# ushio_rp2040.net
KiCad netlist of a schematic drawn in Altium Designer
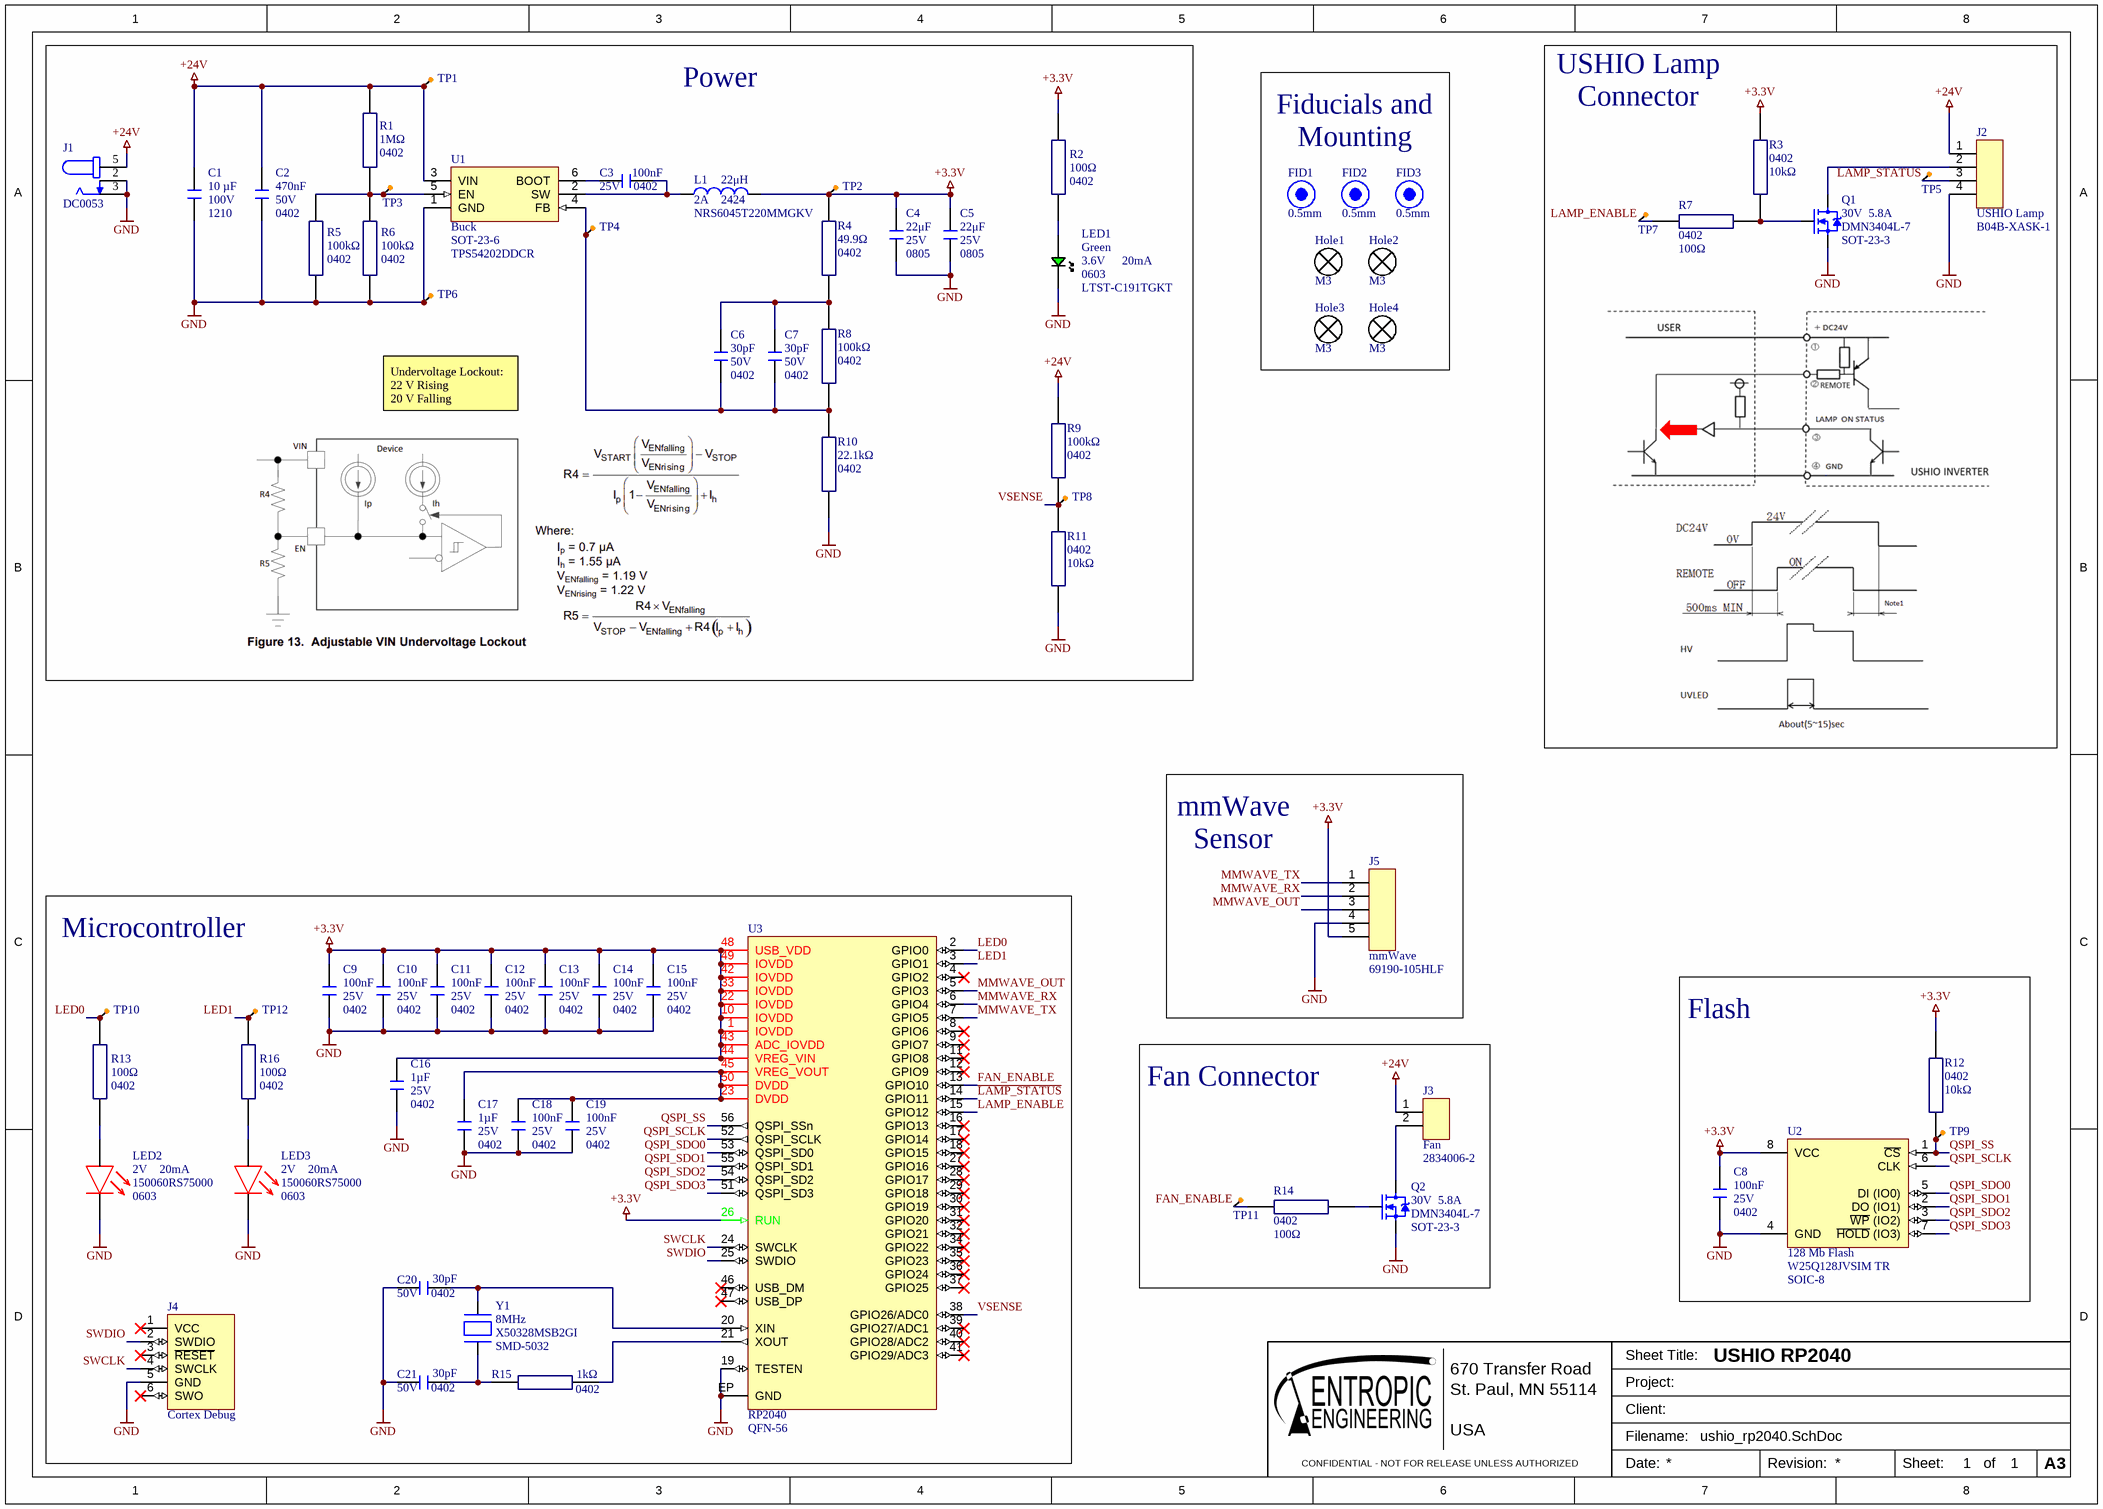
[diagram p0: ushio_rp2040.SchDoc]

(export (version "E")
  (design (tool "Eeschema 10.0.6"))
  (components
    (comp (ref "C1")
      (value "GRM32EC72A106KE05L")
      (footprint "1210_capacitor")
      (description "10 µF, 100 V, 1210 Ceramic capacitor")
      (fields
        (field (name "MANUFACTURER") "Murata")
        (field (name "TOLERANCE") "10%")
        (field (name "VOLTAGE RATING") "100V")
        (field (name "CASE/PACKAGE") "1210")
        (field (name "CAPACITANCE") "10 µF")
      )
      (libsource (lib "ushio_rp2040") (part "GRM32EC72A106KE05L"))
    )
    (comp (ref "C2")
      (value "GRM155R61H474KE11D")
      (footprint "0402_capacitor")
      (description "470 nF, 50 V, X5R, 0402 Chip capacitor")
      (fields
        (field (name "MANUFACTURER") "Murata")
        (field (name "TOLERANCE") "10%")
        (field (name "PACKAGE") "0402")
        (field (name "VOLTAGE RATING (DC)") "50V")
        (field (name "CAPACITANCE") "470nF")
      )
      (libsource (lib "ushio_rp2040") (part "GRM155R61H474KE11D"))
    )
    (comp (ref "C3")
      (value "GRM155R71E104KE14D")
      (footprint "0402_capacitor")
      (description "100 nF, 25 V, X7R, 0402 Chip capacitor")
      (fields
        (field (name "MANUFACTURER") "Murata")
        (field (name "TOLERANCE") "10%")
        (field (name "CASE CODE (IMPERIAL)") "0402")
        (field (name "VOLTAGE") "25V")
        (field (name "CAPACITANCE") "100nF")
      )
      (libsource (lib "ushio_rp2040") (part "GRM155R71E104KE14D"))
    )
    (comp (ref "C4")
      (value "22μF")
      (footprint "0805_capacitor")
      (description "22 μF, 25 V, X5R, 0805 Chip capacitor")
      (fields
        (field (name "MANUFACTURER") "Murata")
        (field (name "MANUFACTURER PART NUMBER") "GRT21BR61E226ME13L")
        (field (name "RATED DC VOLTAGE (URDC)") "25V")
        (field (name "CASE/PACKAGE") "0805")
      )
      (libsource (lib "lamp_controller") (part "GRT21BR61E226ME13L"))
    )
    (comp (ref "C5")
      (value "22μF")
      (footprint "0805_capacitor")
      (description "22 μF, 25 V, X5R, 0805 Chip capacitor")
      (fields
        (field (name "MANUFACTURER") "Murata")
        (field (name "MANUFACTURER PART NUMBER") "GRT21BR61E226ME13L")
        (field (name "RATED DC VOLTAGE (URDC)") "25V")
        (field (name "CASE/PACKAGE") "0805")
      )
      (libsource (lib "lamp_controller") (part "GRT21BR61E226ME13L"))
    )
    (comp (ref "C6")
      (value "30pF")
      (footprint "0402_capacitor")
      (description "30 pF, 50 V, C0G, 0402 Chip capacitor")
      (fields
        (field (name "MANUFACTURER") "Murata")
        (field (name "MANUFACTURER PART NUMBER") "GCM1555C1H300FA16D")
        (field (name "RATED DC VOLTAGE (URDC)") "50V")
        (field (name "CASE/PACKAGE") "0402")
      )
      (libsource (lib "ushio_rp2040") (part "GCM1555C1H300FA16D"))
    )
    (comp (ref "C7")
      (value "30pF")
      (footprint "0402_capacitor")
      (description "30 pF, 50 V, C0G, 0402 Chip capacitor")
      (fields
        (field (name "MANUFACTURER") "Murata")
        (field (name "MANUFACTURER PART NUMBER") "GCM1555C1H300FA16D")
        (field (name "RATED DC VOLTAGE (URDC)") "50V")
        (field (name "CASE/PACKAGE") "0402")
      )
      (libsource (lib "ushio_rp2040") (part "GCM1555C1H300FA16D"))
    )
    (comp (ref "C8")
      (value "GRM155R71E104KE14D")
      (footprint "0402_capacitor")
      (description "100 nF, 25 V, X7R, 0402 Chip capacitor")
      (fields
        (field (name "MANUFACTURER") "Murata")
        (field (name "TOLERANCE") "10%")
        (field (name "CASE CODE (IMPERIAL)") "0402")
        (field (name "VOLTAGE") "25V")
        (field (name "CAPACITANCE") "100nF")
      )
      (libsource (lib "ushio_rp2040") (part "GRM155R71E104KE14D"))
    )
    (comp (ref "C9")
      (value "GRM155R71E104KE14D")
      (footprint "0402_capacitor")
      (description "100 nF, 25 V, X7R, 0402 Chip capacitor")
      (fields
        (field (name "MANUFACTURER") "Murata")
        (field (name "TOLERANCE") "10%")
        (field (name "CASE CODE (IMPERIAL)") "0402")
        (field (name "VOLTAGE") "25V")
        (field (name "CAPACITANCE") "100nF")
      )
      (libsource (lib "ushio_rp2040") (part "GRM155R71E104KE14D"))
    )
    (comp (ref "C10")
      (value "GRM155R71E104KE14D")
      (footprint "0402_capacitor")
      (description "100 nF, 25 V, X7R, 0402 Chip capacitor")
      (fields
        (field (name "MANUFACTURER") "Murata")
        (field (name "TOLERANCE") "10%")
        (field (name "CASE CODE (IMPERIAL)") "0402")
        (field (name "VOLTAGE") "25V")
        (field (name "CAPACITANCE") "100nF")
      )
      (libsource (lib "ushio_rp2040") (part "GRM155R71E104KE14D"))
    )
    (comp (ref "C11")
      (value "GRM155R71E104KE14D")
      (footprint "0402_capacitor")
      (description "100 nF, 25 V, X7R, 0402 Chip capacitor")
      (fields
        (field (name "MANUFACTURER") "Murata")
        (field (name "TOLERANCE") "10%")
        (field (name "CASE CODE (IMPERIAL)") "0402")
        (field (name "VOLTAGE") "25V")
        (field (name "CAPACITANCE") "100nF")
      )
      (libsource (lib "ushio_rp2040") (part "GRM155R71E104KE14D"))
    )
    (comp (ref "C12")
      (value "GRM155R71E104KE14D")
      (footprint "0402_capacitor")
      (description "100 nF, 25 V, X7R, 0402 Chip capacitor")
      (fields
        (field (name "MANUFACTURER") "Murata")
        (field (name "TOLERANCE") "10%")
        (field (name "CASE CODE (IMPERIAL)") "0402")
        (field (name "VOLTAGE") "25V")
        (field (name "CAPACITANCE") "100nF")
      )
      (libsource (lib "ushio_rp2040") (part "GRM155R71E104KE14D"))
    )
    (comp (ref "C13")
      (value "GRM155R71E104KE14D")
      (footprint "0402_capacitor")
      (description "100 nF, 25 V, X7R, 0402 Chip capacitor")
      (fields
        (field (name "MANUFACTURER") "Murata")
        (field (name "TOLERANCE") "10%")
        (field (name "CASE CODE (IMPERIAL)") "0402")
        (field (name "VOLTAGE") "25V")
        (field (name "CAPACITANCE") "100nF")
      )
      (libsource (lib "ushio_rp2040") (part "GRM155R71E104KE14D"))
    )
    (comp (ref "C14")
      (value "GRM155R71E104KE14D")
      (footprint "0402_capacitor")
      (description "100 nF, 25 V, X7R, 0402 Chip capacitor")
      (fields
        (field (name "MANUFACTURER") "Murata")
        (field (name "TOLERANCE") "10%")
        (field (name "CASE CODE (IMPERIAL)") "0402")
        (field (name "VOLTAGE") "25V")
        (field (name "CAPACITANCE") "100nF")
      )
      (libsource (lib "ushio_rp2040") (part "GRM155R71E104KE14D"))
    )
    (comp (ref "C15")
      (value "GRM155R71E104KE14D")
      (footprint "0402_capacitor")
      (description "100 nF, 25 V, X7R, 0402 Chip capacitor")
      (fields
        (field (name "MANUFACTURER") "Murata")
        (field (name "TOLERANCE") "10%")
        (field (name "CASE CODE (IMPERIAL)") "0402")
        (field (name "VOLTAGE") "25V")
        (field (name "CAPACITANCE") "100nF")
      )
      (libsource (lib "ushio_rp2040") (part "GRM155R71E104KE14D"))
    )
    (comp (ref "C16")
      (value "GRM155R61E105KA12D")
      (footprint "0402_capacitor")
      (description "1 µF, 25 V, X5R, 0402 Chip capacitor")
      (fields
        (field (name "MANUFACTURER") "Murata")
        (field (name "HOUSE_PART_NUMBER") "C-1uF-0402-002")
        (field (name "SIZE CODE") "0402")
        (field (name "CAPACITANCE") "1µF")
        (field (name "VOLTAGE") "25V")
      )
      (libsource (lib "ushio_rp2040") (part "GRM155R61E105KA12D"))
    )
    (comp (ref "C17")
      (value "GRM155R61E105KA12D")
      (footprint "0402_capacitor")
      (description "1 µF, 25 V, X5R, 0402 Chip capacitor")
      (fields
        (field (name "MANUFACTURER") "Murata")
        (field (name "HOUSE_PART_NUMBER") "C-1uF-0402-002")
        (field (name "SIZE CODE") "0402")
        (field (name "CAPACITANCE") "1µF")
        (field (name "VOLTAGE") "25V")
      )
      (libsource (lib "ushio_rp2040") (part "GRM155R61E105KA12D"))
    )
    (comp (ref "C18")
      (value "GRM155R71E104KE14D")
      (footprint "0402_capacitor")
      (description "100 nF, 25 V, X7R, 0402 Chip capacitor")
      (fields
        (field (name "MANUFACTURER") "Murata")
        (field (name "TOLERANCE") "10%")
        (field (name "CASE CODE (IMPERIAL)") "0402")
        (field (name "VOLTAGE") "25V")
        (field (name "CAPACITANCE") "100nF")
      )
      (libsource (lib "ushio_rp2040") (part "GRM155R71E104KE14D"))
    )
    (comp (ref "C19")
      (value "GRM155R71E104KE14D")
      (footprint "0402_capacitor")
      (description "100 nF, 25 V, X7R, 0402 Chip capacitor")
      (fields
        (field (name "MANUFACTURER") "Murata")
        (field (name "TOLERANCE") "10%")
        (field (name "CASE CODE (IMPERIAL)") "0402")
        (field (name "VOLTAGE") "25V")
        (field (name "CAPACITANCE") "100nF")
      )
      (libsource (lib "ushio_rp2040") (part "GRM155R71E104KE14D"))
    )
    (comp (ref "C20")
      (value "30pF")
      (footprint "0402_capacitor")
      (description "30 pF, 50 V, C0G, 0402 Chip capacitor")
      (fields
        (field (name "MANUFACTURER") "Murata")
        (field (name "MANUFACTURER PART NUMBER") "GCM1555C1H300FA16D")
        (field (name "RATED DC VOLTAGE (URDC)") "50V")
        (field (name "CASE/PACKAGE") "0402")
      )
      (libsource (lib "ushio_rp2040") (part "GCM1555C1H300FA16D"))
    )
    (comp (ref "C21")
      (value "30pF")
      (footprint "0402_capacitor")
      (description "30 pF, 50 V, C0G, 0402 Chip capacitor")
      (fields
        (field (name "MANUFACTURER") "Murata")
        (field (name "MANUFACTURER PART NUMBER") "GCM1555C1H300FA16D")
        (field (name "RATED DC VOLTAGE (URDC)") "50V")
        (field (name "CASE/PACKAGE") "0402")
      )
      (libsource (lib "ushio_rp2040") (part "GCM1555C1H300FA16D"))
    )
    (comp (ref "FID1")
      (value "FID?")
      (footprint "fiducial-0.5")
      (description "0.5mm round fiducial")
      (fields (field (name "PACKAGE") "0.5mm"))
      (libsource (lib "ushio_rp2040") (part "fiducial-0.5"))
    )
    (comp (ref "FID2")
      (value "FID?")
      (footprint "fiducial-0.5")
      (description "0.5mm round fiducial")
      (fields (field (name "PACKAGE") "0.5mm"))
      (libsource (lib "ushio_rp2040") (part "fiducial-0.5"))
    )
    (comp (ref "FID3")
      (value "FID?")
      (footprint "fiducial-0.5")
      (description "0.5mm round fiducial")
      (fields (field (name "PACKAGE") "0.5mm"))
      (libsource (lib "ushio_rp2040") (part "fiducial-0.5"))
    )
    (comp (ref "Hole1")
      (value "M3")
      (footprint "m3_hole_no_pad")
      (description "M3 clearance hole")
      (libsource (lib "ushio_rp2040") (part "m3_hole_no_pad"))
    )
    (comp (ref "Hole2")
      (value "M3")
      (footprint "m3_hole_no_pad")
      (description "M3 clearance hole")
      (libsource (lib "ushio_rp2040") (part "m3_hole_no_pad"))
    )
    (comp (ref "Hole3")
      (value "M3")
      (footprint "m3_hole_no_pad")
      (description "M3 clearance hole")
      (libsource (lib "ushio_rp2040") (part "m3_hole_no_pad"))
    )
    (comp (ref "Hole4")
      (value "M3")
      (footprint "m3_hole_no_pad")
      (description "M3 clearance hole")
      (libsource (lib "ushio_rp2040") (part "m3_hole_no_pad"))
    )
    (comp (ref "J1")
      (value "DC0053")
      (footprint "DC0053")
      (description "5.5 mm x 2 mm Barrel jack")
      (fields (field (name "MANUFACTURER") "SHOU HAN") (field (name "MANUFACTURER PART NUMBER") "DC0053"))
      (libsource (lib "ushio_rp2040") (part "DC0053"))
    )
    (comp (ref "J2")
      (value "USHIO Lamp")
      (footprint "B04B-XASK-1")
      (description "4-pin JST XA header, 2.5mm pitch, through-hole")
      (fields (field (name "MANUFACTURER") "JST") (field (name "MANUFACTURER PART NUMBER") "B04B-XASK-1"))
      (libsource (lib "ushio_rp2040") (part "B04B-XASK-1"))
    )
    (comp (ref "J3")
      (value "Fan")
      (footprint "2834006-2")
      (description "2-Pin Barrier Strip Terminal Block")
      (fields
        (field (name "MANUFACTURER") "TE Connectivity")
        (field (name "MANUFACTURER PART NUMBER") "2834006-2")
      )
      (libsource (lib "ushio_rp2040") (part "2834006-2"))
    )
    (comp (ref "J4")
      (value "Cortex Debug")
      (footprint "debug_header")
      (description "Tag-connect 6-pin pogo header")
      (libsource (lib "ushio_rp2040") (part "debug_header"))
    )
    (comp (ref "J5")
      (value "mmWave")
      (footprint "69190-105HLF")
      (description "5-pin 0.1\" unshrouded header pins")
      (fields
        (field (name "MANUFACTURER") "Amphenol ICC / FCI")
        (field (name "MANUFACTURER PART NUMBER") "69190-105HLF")
      )
      (libsource (lib "ushio_rp2040") (part "69190-105HLF"))
    )
    (comp (ref "L1")
      (value "NRS6045T220MMGKV")
      (footprint "2424_inductor")
      (description "22 μH, 2 A, 20%, 2424 Inductor")
      (fields
        (field (name "MANUFACTURER") "Taiyo Yuden")
        (field (name "TOLERANCE") "20%")
        (field (name "MANUFACTURER PART NUMBER") "NRS6045T220MMGKV")
        (field (name "CASE/SIZE CODE") "2424")
        (field (name "MAX CURRENT RATING") "2A")
        (field (name "INDUCTANCE-NOM (L)") "22μH")
      )
      (libsource (lib "lamp_controller") (part "NRS6045T220MMGKV"))
    )
    (comp (ref "LED1")
      (value "LTST-C191TGKT")
      (footprint "0603_diode")
      (description "Green LED, 0603")
      (fields
        (field (name "MANUFACTURER") "Vishay Lite-On")
        (field (name "FORWARD CURRENT-MAX") "20mA")
        (field (name "FORWARD VOLTAGE-MAX") "3.6V")
        (field (name "COLOR") "Green")
        (field (name "PACKAGE") "0603")
        (field (name "MANUFACTURER PART NUMBER") "LTST-C191TGKT")
      )
      (libsource (lib "lamp_control") (part "LTST-C191TGKT"))
    )
    (comp (ref "LED2")
      (value "150060RS75000")
      (footprint "0603_diode")
      (description "Red 0603 LED")
      (fields
        (field (name "MANUFACTURER") "Wurth Electronics")
        (field (name "HOUSE_PART_NUMBER") "LED-red-0603-002")
        (field (name "FORWARD CURRENT") "20mA")
        (field (name "FORWARD VOLTAGE") "2V")
        (field (name "PACKAGE") "0603")
        (field (name "MANUFACTURER PART NUMBER") "150060RS75000")
      )
      (libsource (lib "advanced_wireless_6950_dock") (part "150060RS75000"))
    )
    (comp (ref "LED3")
      (value "150060RS75000")
      (footprint "0603_diode")
      (description "Red 0603 LED")
      (fields
        (field (name "MANUFACTURER") "Wurth Electronics")
        (field (name "HOUSE_PART_NUMBER") "LED-red-0603-002")
        (field (name "FORWARD CURRENT") "20mA")
        (field (name "FORWARD VOLTAGE") "2V")
        (field (name "PACKAGE") "0603")
        (field (name "MANUFACTURER PART NUMBER") "150060RS75000")
      )
      (libsource (lib "advanced_wireless_6950_dock") (part "150060RS75000"))
    )
    (comp (ref "Q1")
      (value "DMN3404L-7")
      (footprint "SOT-23-3")
      (description "N-FET, 30 V, 5.8 A, SOT-23-3")
      (fields
        (field (name "MANUFACTURER") "Diodes")
        (field (name "PACKAGE") "SOT-23-3")
        (field (name "DS BREAKDOWN VOLTAGE-MIN") "30V")
        (field (name "DRAIN CURRENT-MAX (ID)") "5.8A")
        (field (name "MANUFACTURER PART NUMBER") "DMN3404L-7")
      )
      (libsource (lib "ushio_rp2040") (part "DMN3404L-7"))
    )
    (comp (ref "Q2")
      (value "DMN3404L-7")
      (footprint "SOT-23-3")
      (description "N-FET, 30 V, 5.8 A, SOT-23-3")
      (fields
        (field (name "MANUFACTURER") "Diodes")
        (field (name "PACKAGE") "SOT-23-3")
        (field (name "DS BREAKDOWN VOLTAGE-MIN") "30V")
        (field (name "DRAIN CURRENT-MAX (ID)") "5.8A")
        (field (name "MANUFACTURER PART NUMBER") "DMN3404L-7")
      )
      (libsource (lib "ushio_rp2040") (part "DMN3404L-7"))
    )
    (comp (ref "R1")
      (value "RC0402FR-071ML")
      (footprint "0402_resistor")
      (description "1 MΩ, 1%, 0402 Resistor")
      (fields
        (field (name "MANUFACTURER") "Yageo")
        (field (name "TOLERANCE") "1%")
        (field (name "SIZE CODE") "0402")
        (field (name "RESISTANCE") "1MΩ")
      )
      (libsource (lib "ushio_rp2040") (part "RC0402FR-071ML"))
    )
    (comp (ref "R2")
      (value "RMCF0402FT100R")
      (footprint "0402_resistor")
      (description "100 Ω, 0402 Chip resistor")
      (fields
        (field (name "MANUFACTURER") "Stackpole Electronics")
        (field (name "TOLERANCE") "1%")
        (field (name "CASE CODE (IMPERIAL)") "0402")
        (field (name "RESISTANCE") "100Ω")
      )
      (libsource (lib "ushio_rp2040") (part "RMCF0402FT100R"))
    )
    (comp (ref "R3")
      (value "RMCF0402FT10K0")
      (footprint "0402_resistor")
      (description "10 kΩ, 0402 Chip resistor")
      (fields
        (field (name "MANUFACTURER") "Stackpole Electronics")
        (field (name "TOLERANCE") "1%")
        (field (name "CASE CODE (IMPERIAL)") "0402")
        (field (name "RESISTANCE") "10kΩ")
      )
      (libsource (lib "ushio_rp2040") (part "RMCF0402FT10K0"))
    )
    (comp (ref "R4")
      (value "RMCF0402FT49R9")
      (footprint "0402_resistor")
      (description "49.9 Ω, 0402 Chip resistor")
      (fields
        (field (name "MANUFACTURER") "Stackpole Electronics")
        (field (name "TOLERANCE") "1%")
        (field (name "RESISTANCE") "49.9Ω")
        (field (name "CASE CODE (IMPERIAL)") "0402")
      )
      (libsource (lib "ushio_rp2040") (part "RMCF0402FT49R9"))
    )
    (comp (ref "R5")
      (value "100kΩ")
      (footprint "0402_resistor")
      (description "100 kΩ, 0402 Chip resistor")
      (fields
        (field (name "MANUFACTURER") "Stackpole Electronics")
        (field (name "MANUFACTURER PART NUMBER") "RMCF0402FT100K")
        (field (name "CASE/PACKAGE") "0402")
      )
      (libsource (lib "lamp_controller") (part "RMCF0402FT100K"))
    )
    (comp (ref "R6")
      (value "100kΩ")
      (footprint "0402_resistor")
      (description "100 kΩ, 0402 Chip resistor")
      (fields
        (field (name "MANUFACTURER") "Stackpole Electronics")
        (field (name "MANUFACTURER PART NUMBER") "RMCF0402FT100K")
        (field (name "CASE/PACKAGE") "0402")
      )
      (libsource (lib "lamp_controller") (part "RMCF0402FT100K"))
    )
    (comp (ref "R7")
      (value "RMCF0402FT100R")
      (footprint "0402_resistor")
      (description "100 Ω, 0402 Chip resistor")
      (fields
        (field (name "MANUFACTURER") "Stackpole Electronics")
        (field (name "TOLERANCE") "1%")
        (field (name "CASE CODE (IMPERIAL)") "0402")
        (field (name "RESISTANCE") "100Ω")
      )
      (libsource (lib "ushio_rp2040") (part "RMCF0402FT100R"))
    )
    (comp (ref "R8")
      (value "100kΩ")
      (footprint "0402_resistor")
      (description "100 kΩ, 0402 Chip resistor")
      (fields
        (field (name "MANUFACTURER") "Stackpole Electronics")
        (field (name "MANUFACTURER PART NUMBER") "RMCF0402FT100K")
        (field (name "CASE/PACKAGE") "0402")
      )
      (libsource (lib "lamp_controller") (part "RMCF0402FT100K"))
    )
    (comp (ref "R9")
      (value "100kΩ")
      (footprint "0402_resistor")
      (description "100 kΩ, 0402 Chip resistor")
      (fields
        (field (name "MANUFACTURER") "Stackpole Electronics")
        (field (name "MANUFACTURER PART NUMBER") "RMCF0402FT100K")
        (field (name "CASE/PACKAGE") "0402")
      )
      (libsource (lib "lamp_controller") (part "RMCF0402FT100K"))
    )
    (comp (ref "R10")
      (value "22.1kΩ")
      (footprint "0402_resistor")
      (description "22.1 kΩ, 1%, 0402 Chip resistor")
      (fields
        (field (name "MANUFACTURER") "Stackpole Electronics")
        (field (name "MANUFACTURER PART NUMBER") "RMCF0402FT22K1")
        (field (name "CASE/PACKAGE") "0402")
      )
      (libsource (lib "lamp_controller") (part "RMCF0402FT22K1"))
    )
    (comp (ref "R11")
      (value "RMCF0402FT10K0")
      (footprint "0402_resistor")
      (description "10 kΩ, 0402 Chip resistor")
      (fields
        (field (name "MANUFACTURER") "Stackpole Electronics")
        (field (name "TOLERANCE") "1%")
        (field (name "CASE CODE (IMPERIAL)") "0402")
        (field (name "RESISTANCE") "10kΩ")
      )
      (libsource (lib "ushio_rp2040") (part "RMCF0402FT10K0"))
    )
    (comp (ref "R12")
      (value "RMCF0402FT10K0")
      (footprint "0402_resistor")
      (description "10 kΩ, 0402 Chip resistor")
      (fields
        (field (name "MANUFACTURER") "Stackpole Electronics")
        (field (name "TOLERANCE") "1%")
        (field (name "CASE CODE (IMPERIAL)") "0402")
        (field (name "RESISTANCE") "10kΩ")
      )
      (libsource (lib "ushio_rp2040") (part "RMCF0402FT10K0"))
    )
    (comp (ref "R13")
      (value "RMCF0402FT100R")
      (footprint "0402_resistor")
      (description "100 Ω, 0402 Chip resistor")
      (fields
        (field (name "MANUFACTURER") "Stackpole Electronics")
        (field (name "TOLERANCE") "1%")
        (field (name "CASE CODE (IMPERIAL)") "0402")
        (field (name "RESISTANCE") "100Ω")
      )
      (libsource (lib "ushio_rp2040") (part "RMCF0402FT100R"))
    )
    (comp (ref "R14")
      (value "RMCF0402FT100R")
      (footprint "0402_resistor")
      (description "100 Ω, 0402 Chip resistor")
      (fields
        (field (name "MANUFACTURER") "Stackpole Electronics")
        (field (name "TOLERANCE") "1%")
        (field (name "CASE CODE (IMPERIAL)") "0402")
        (field (name "RESISTANCE") "100Ω")
      )
      (libsource (lib "ushio_rp2040") (part "RMCF0402FT100R"))
    )
    (comp (ref "R15")
      (value "CR0402-FX-1001GLF")
      (footprint "0402_resistor")
      (description "1 kΩ, 0402 Chip resistor")
      (fields
        (field (name "MANUFACTURER") "Bourns")
        (field (name "TOLERANCE") "1%")
        (field (name "SIZE CODE") "0402")
        (field (name "RESISTANCE") "1kΩ")
      )
      (libsource (lib "ushio_rp2040") (part "CR0402-FX-1001GLF"))
    )
    (comp (ref "R16")
      (value "RMCF0402FT100R")
      (footprint "0402_resistor")
      (description "100 Ω, 0402 Chip resistor")
      (fields
        (field (name "MANUFACTURER") "Stackpole Electronics")
        (field (name "TOLERANCE") "1%")
        (field (name "CASE CODE (IMPERIAL)") "0402")
        (field (name "RESISTANCE") "100Ω")
      )
      (libsource (lib "ushio_rp2040") (part "RMCF0402FT100R"))
    )
    (comp (ref "TP1")
      (value "test_point-1")
      (footprint "test_point-1")
      (description "Test point")
      (libsource (lib "ushio_rp2040") (part "test_point-1"))
    )
    (comp (ref "TP2")
      (value "test_point-1")
      (footprint "test_point-1")
      (description "Test point")
      (libsource (lib "ushio_rp2040") (part "test_point-1"))
    )
    (comp (ref "TP3")
      (value "test_point-1")
      (footprint "test_point-1")
      (description "Test point")
      (libsource (lib "ushio_rp2040") (part "test_point-1"))
    )
    (comp (ref "TP4")
      (value "test_point-1")
      (footprint "test_point-1")
      (description "Test point")
      (libsource (lib "ushio_rp2040") (part "test_point-1"))
    )
    (comp (ref "TP5")
      (value "test_point-1")
      (footprint "test_point-1")
      (description "Test point")
      (libsource (lib "ushio_rp2040") (part "test_point-1"))
    )
    (comp (ref "TP6")
      (value "test_point-1")
      (footprint "test_point-1")
      (description "Test point")
      (libsource (lib "ushio_rp2040") (part "test_point-1"))
    )
    (comp (ref "TP7")
      (value "test_point-1")
      (footprint "test_point-1")
      (description "Test point")
      (libsource (lib "ushio_rp2040") (part "test_point-1"))
    )
    (comp (ref "TP8")
      (value "test_point-1")
      (footprint "test_point-1")
      (description "Test point")
      (libsource (lib "ushio_rp2040") (part "test_point-1"))
    )
    (comp (ref "TP9")
      (value "test_point-1")
      (footprint "test_point-1")
      (description "Test point")
      (libsource (lib "ushio_rp2040") (part "test_point-1"))
    )
    (comp (ref "TP10")
      (value "test_point-1")
      (footprint "test_point-1")
      (description "Test point")
      (libsource (lib "ushio_rp2040") (part "test_point-1"))
    )
    (comp (ref "TP11")
      (value "test_point-1")
      (footprint "test_point-1")
      (description "Test point")
      (libsource (lib "ushio_rp2040") (part "test_point-1"))
    )
    (comp (ref "TP12")
      (value "test_point-1")
      (footprint "test_point-1")
      (description "Test point")
      (libsource (lib "ushio_rp2040") (part "test_point-1"))
    )
    (comp (ref "U1")
      (value "Buck")
      (footprint "SOT-23-6")
      (description "Switching Regulator, Current-mode, 2A, 500kHz Switching Freq-Max, PDSO6")
      (fields
        (field (name "MANUFACTURER") "Texas Instruments")
        (field (name "CASE/PACKAGE") "SOT-23-6")
        (field (name "MANUFACTURER PART NUMBER") "TPS54202DDCR")
      )
      (libsource (lib "ushio_rp2040") (part "TPS54202DDCR"))
    )
    (comp (ref "U2")
      (value "128 Mb Flash")
      (footprint "SOIC-8_wide")
      (description "128Mb SPI flash memory")
      (fields
        (field (name "MANUFACTURER") "Winbond")
        (field (name "HOUSE_PART_NUMBER") "W25Q128JVSIM")
        (field (name "MANUFACTURER PART NUMBER") "W25Q128JVSIM TR")
        (field (name "CASE/PACKAGE") "SOIC-8")
      )
      (libsource (lib "ushio_rp2040") (part "W25Q128JVSIM TR"))
    )
    (comp (ref "U3")
      (value "RP2040")
      (footprint "QFN-56")
      (description "Raspberry Pi microcontroller, QFN-56")
      (fields
        (field (name "MANUFACTURER") "Raspberry Pi")
        (field (name "MANUFACTURER PART NUMBER") "RP2040")
        (field (name "PACKAGE") "QFN-56")
      )
      (libsource (lib "ushio_rp2040") (part "RP2040"))
    )
    (comp (ref "Y1")
      (value "X50328MSB2GI")
      (footprint "SMD-5032")
      (description "8 MHz crystal, 20 pF, ±50ppm, SMD-5032")
      (fields
        (field (name "MANUFACTURER") "YXC")
        (field (name "FREQUENCY") "8MHz")
        (field (name "PACKAGE") "SMD-5032")
        (field (name "MANUFACTURER PART NUMBER") "X50328MSB2GI")
      )
      (libsource (lib "ushio_rp2040") (part "X50328MSB2GI"))
    )
  )
  (nets
    (net (code "1") (name "+3.3V") (class "Default")
      (node (ref "C10") (pin "2") (pinfunction "2_2") (pintype "passive"))
      (node (ref "C11") (pin "2") (pinfunction "2_2") (pintype "passive"))
      (node (ref "C12") (pin "2") (pinfunction "2_2") (pintype "passive"))
      (node (ref "C13") (pin "2") (pinfunction "2_2") (pintype "passive"))
      (node (ref "C14") (pin "2") (pinfunction "2_2") (pintype "passive"))
      (node (ref "C15") (pin "2") (pinfunction "2_2") (pintype "passive"))
      (node (ref "C16") (pin "2") (pinfunction "2_2") (pintype "passive"))
      (node (ref "C4") (pin "2") (pinfunction "2_2") (pintype "passive"))
      (node (ref "C5") (pin "2") (pinfunction "2_2") (pintype "passive"))
      (node (ref "C8") (pin "2") (pinfunction "2_2") (pintype "passive"))
      (node (ref "C9") (pin "2") (pinfunction "2_2") (pintype "passive"))
      (node (ref "J5") (pin "5") (pintype "passive"))
      (node (ref "L1") (pin "2") (pinfunction "2_2") (pintype "passive"))
      (node (ref "R12") (pin "2") (pinfunction "2_2") (pintype "passive"))
      (node (ref "R2") (pin "2") (pinfunction "2_2") (pintype "passive"))
      (node (ref "R3") (pin "1") (pinfunction "1_1") (pintype "passive"))
      (node (ref "R4") (pin "2") (pinfunction "2_2") (pintype "passive"))
      (node (ref "TP2") (pin "1") (pinfunction "1_1") (pintype "passive"))
      (node (ref "U2") (pin "8") (pinfunction "VCC_8") (pintype "power_in"))
      (node (ref "U3") (pin "1") (pinfunction "IOVDD_1") (pintype "power_in"))
      (node (ref "U3") (pin "10") (pinfunction "IOVDD_10") (pintype "power_in"))
      (node (ref "U3") (pin "22") (pinfunction "IOVDD_22") (pintype "power_in"))
      (node (ref "U3") (pin "26") (pinfunction "RUN_26") (pintype "input"))
      (node (ref "U3") (pin "33") (pinfunction "IOVDD_33") (pintype "power_in"))
      (node (ref "U3") (pin "42") (pinfunction "IOVDD_42") (pintype "power_in"))
      (node (ref "U3") (pin "43") (pinfunction "ADC_IOVDD_43") (pintype "power_in"))
      (node (ref "U3") (pin "44") (pinfunction "VREG_VIN_44") (pintype "power_in"))
      (node (ref "U3") (pin "48") (pinfunction "USB_VDD_48") (pintype "power_in"))
      (node (ref "U3") (pin "49") (pinfunction "IOVDD_49") (pintype "power_in"))
    )
    (net (code "2") (name "+24V") (class "Default")
      (node (ref "C1") (pin "2") (pinfunction "2_2") (pintype "passive"))
      (node (ref "C2") (pin "2") (pinfunction "2_2") (pintype "passive"))
      (node (ref "J1") (pin "5") (pinfunction "TIP_5") (pintype "passive"))
      (node (ref "J2") (pin "1") (pintype "passive"))
      (node (ref "J3") (pin "1") (pintype "passive"))
      (node (ref "R1") (pin "2") (pinfunction "2_2") (pintype "passive"))
      (node (ref "R9") (pin "2") (pinfunction "2_2") (pintype "passive"))
      (node (ref "TP1") (pin "1") (pinfunction "1_1") (pintype "passive"))
      (node (ref "U1") (pin "3") (pinfunction "VIN_3") (pintype "power_in"))
    )
    (net (code "3") (name "/FAN_ENABLE") (class "Default")
      (node (ref "R14") (pin "1") (pinfunction "1_1") (pintype "passive"))
      (node (ref "TP11") (pin "1") (pinfunction "1_1") (pintype "passive"))
      (node (ref "U3") (pin "13") (pinfunction "GPIO10_13") (pintype "bidirectional"))
    )
    (net (code "4") (name "/LAMP_ENABLE") (class "Default")
      (node (ref "R7") (pin "1") (pinfunction "1_1") (pintype "passive"))
      (node (ref "TP7") (pin "1") (pinfunction "1_1") (pintype "passive"))
      (node (ref "U3") (pin "15") (pinfunction "GPIO12_15") (pintype "bidirectional"))
    )
    (net (code "5") (name "/LAMP_STATUS") (class "Default")
      (node (ref "J2") (pin "3") (pintype "passive"))
      (node (ref "TP5") (pin "1") (pinfunction "1_1") (pintype "passive"))
      (node (ref "U3") (pin "14") (pinfunction "GPIO11_14") (pintype "bidirectional"))
    )
    (net (code "6") (name "/LED0") (class "Default")
      (node (ref "R13") (pin "2") (pinfunction "2_2") (pintype "passive"))
      (node (ref "TP10") (pin "1") (pinfunction "1_1") (pintype "passive"))
      (node (ref "U3") (pin "2") (pinfunction "GPIO0_2") (pintype "bidirectional"))
    )
    (net (code "7") (name "/LED1") (class "Default")
      (node (ref "R16") (pin "2") (pinfunction "2_2") (pintype "passive"))
      (node (ref "TP12") (pin "1") (pinfunction "1_1") (pintype "passive"))
      (node (ref "U3") (pin "3") (pinfunction "GPIO1_3") (pintype "bidirectional"))
    )
    (net (code "8") (name "/MMWAVE_OUT") (class "Default")
      (node (ref "J5") (pin "3") (pintype "passive"))
      (node (ref "U3") (pin "5") (pinfunction "GPIO3_5") (pintype "bidirectional"))
    )
    (net (code "9") (name "/MMWAVE_RX") (class "Default")
      (node (ref "J5") (pin "2") (pintype "passive"))
      (node (ref "U3") (pin "6") (pinfunction "GPIO4_6") (pintype "bidirectional"))
    )
    (net (code "10") (name "/MMWAVE_TX") (class "Default")
      (node (ref "J5") (pin "1") (pintype "passive"))
      (node (ref "U3") (pin "7") (pinfunction "GPIO5_7") (pintype "bidirectional"))
    )
    (net (code "11") (name "/QSPI_SCLK") (class "Default")
      (node (ref "U2") (pin "6") (pinfunction "CLK_6") (pintype "input"))
      (node (ref "U3") (pin "52") (pinfunction "QSPI_SCLK_52") (pintype "output"))
    )
    (net (code "12") (name "/QSPI_SDO0") (class "Default")
      (node (ref "U2") (pin "5") (pinfunction "DI_(IO0)_5") (pintype "bidirectional"))
      (node (ref "U3") (pin "53") (pinfunction "QSPI_SD0_53") (pintype "bidirectional"))
    )
    (net (code "13") (name "/QSPI_SDO1") (class "Default")
      (node (ref "U2") (pin "2") (pinfunction "DO_(IO1)_2") (pintype "bidirectional"))
      (node (ref "U3") (pin "55") (pinfunction "QSPI_SD1_55") (pintype "bidirectional"))
    )
    (net (code "14") (name "/QSPI_SDO2") (class "Default")
      (node (ref "U2") (pin "3") (pinfunction "~{WP}_(IO2)_3") (pintype "bidirectional"))
      (node (ref "U3") (pin "54") (pinfunction "QSPI_SD2_54") (pintype "bidirectional"))
    )
    (net (code "15") (name "/QSPI_SDO3") (class "Default")
      (node (ref "U2") (pin "7") (pinfunction "~{HOLD}_(IO3)_7") (pintype "bidirectional"))
      (node (ref "U3") (pin "51") (pinfunction "QSPI_SD3_51") (pintype "bidirectional"))
    )
    (net (code "16") (name "/QSPI_SS") (class "Default")
      (node (ref "R12") (pin "1") (pinfunction "1_1") (pintype "passive"))
      (node (ref "TP9") (pin "1") (pinfunction "1_1") (pintype "passive"))
      (node (ref "U2") (pin "1") (pinfunction "~{CS}_1") (pintype "input"))
      (node (ref "U3") (pin "56") (pinfunction "QSPI_SSn_56") (pintype "output"))
    )
    (net (code "17") (name "/SWCLK") (class "Default")
      (node (ref "J4") (pin "4") (pinfunction "SWCLK_4") (pintype "bidirectional"))
      (node (ref "U3") (pin "24") (pinfunction "SWCLK_24") (pintype "bidirectional"))
    )
    (net (code "18") (name "/SWDIO") (class "Default")
      (node (ref "J4") (pin "2") (pinfunction "SWDIO_2") (pintype "bidirectional"))
      (node (ref "U3") (pin "25") (pinfunction "SWDIO_25") (pintype "bidirectional"))
    )
    (net (code "19") (name "/VSENSE") (class "Default")
      (node (ref "R11") (pin "2") (pinfunction "2_2") (pintype "passive"))
      (node (ref "R9") (pin "1") (pinfunction "1_1") (pintype "passive"))
      (node (ref "TP8") (pin "1") (pinfunction "1_1") (pintype "passive"))
      (node (ref "U3") (pin "38") (pinfunction "GPIO26/ADC0_38") (pintype "bidirectional"))
    )
    (net (code "20") (name "GND") (class "Default")
      (node (ref "C1") (pin "1") (pinfunction "1_1") (pintype "passive"))
      (node (ref "C10") (pin "1") (pinfunction "1_1") (pintype "passive"))
      (node (ref "C11") (pin "1") (pinfunction "1_1") (pintype "passive"))
      (node (ref "C12") (pin "1") (pinfunction "1_1") (pintype "passive"))
      (node (ref "C13") (pin "1") (pinfunction "1_1") (pintype "passive"))
      (node (ref "C14") (pin "1") (pinfunction "1_1") (pintype "passive"))
      (node (ref "C15") (pin "1") (pinfunction "1_1") (pintype "passive"))
      (node (ref "C16") (pin "1") (pinfunction "1_1") (pintype "passive"))
      (node (ref "C17") (pin "1") (pinfunction "1_1") (pintype "passive"))
      (node (ref "C18") (pin "1") (pinfunction "1_1") (pintype "passive"))
      (node (ref "C19") (pin "1") (pinfunction "1_1") (pintype "passive"))
      (node (ref "C2") (pin "1") (pinfunction "1_1") (pintype "passive"))
      (node (ref "C20") (pin "1") (pinfunction "1_1") (pintype "passive"))
      (node (ref "C21") (pin "1") (pinfunction "1_1") (pintype "passive"))
      (node (ref "C4") (pin "1") (pinfunction "1_1") (pintype "passive"))
      (node (ref "C5") (pin "1") (pinfunction "1_1") (pintype "passive"))
      (node (ref "C8") (pin "1") (pinfunction "1_1") (pintype "passive"))
      (node (ref "C9") (pin "1") (pinfunction "1_1") (pintype "passive"))
      (node (ref "J1") (pin "2") (pinfunction "SWITCH_2") (pintype "passive"))
      (node (ref "J1") (pin "3") (pinfunction "SLEEVE_3") (pintype "passive"))
      (node (ref "J2") (pin "4") (pintype "passive"))
      (node (ref "J4") (pin "5") (pinfunction "GND_5") (pintype "power_in"))
      (node (ref "J5") (pin "4") (pintype "passive"))
      (node (ref "LED1") (pin "2") (pinfunction "K_2") (pintype "passive"))
      (node (ref "LED2") (pin "2") (pinfunction "2_2") (pintype "passive"))
      (node (ref "LED3") (pin "2") (pinfunction "2_2") (pintype "passive"))
      (node (ref "Q1") (pin "2") (pinfunction "S_2") (pintype "passive"))
      (node (ref "Q2") (pin "2") (pinfunction "S_2") (pintype "passive"))
      (node (ref "R10") (pin "1") (pinfunction "1_1") (pintype "passive"))
      (node (ref "R11") (pin "1") (pinfunction "1_1") (pintype "passive"))
      (node (ref "R5") (pin "1") (pinfunction "1_1") (pintype "passive"))
      (node (ref "R6") (pin "1") (pinfunction "1_1") (pintype "passive"))
      (node (ref "TP6") (pin "1") (pinfunction "1_1") (pintype "passive"))
      (node (ref "U1") (pin "1") (pinfunction "GND_1") (pintype "power_in"))
      (node (ref "U2") (pin "4") (pinfunction "GND_4") (pintype "power_in"))
      (node (ref "U3") (pin "19") (pinfunction "TESTEN_19") (pintype "bidirectional"))
      (node (ref "U3") (pin "EP") (pinfunction "GND_EP") (pintype "power_in"))
    )
    (net (code "21") (name "Net-(C6-Pad2)") (class "Default")
      (node (ref "C6") (pin "2") (pinfunction "2_2") (pintype "passive"))
      (node (ref "C7") (pin "2") (pinfunction "2_2") (pintype "passive"))
      (node (ref "R4") (pin "1") (pinfunction "1_1") (pintype "passive"))
      (node (ref "R8") (pin "2") (pinfunction "2_2") (pintype "passive"))
    )
    (net (code "22") (name "Net-(C21-Pad2)") (class "Default")
      (node (ref "C21") (pin "2") (pinfunction "2_2") (pintype "passive"))
      (node (ref "R15") (pin "1") (pinfunction "1_1") (pintype "passive"))
      (node (ref "Y1") (pin "1") (pinfunction "1_1") (pintype "passive"))
    )
    (net (code "23") (name "Net-(LED1-A)") (class "Default")
      (node (ref "LED1") (pin "1") (pinfunction "A_1") (pintype "passive"))
      (node (ref "R2") (pin "1") (pinfunction "1_1") (pintype "passive"))
    )
    (net (code "24") (name "Net-(LED2-Pad1)") (class "Default")
      (node (ref "LED2") (pin "1") (pinfunction "1_1") (pintype "passive"))
      (node (ref "R13") (pin "1") (pinfunction "1_1") (pintype "passive"))
    )
    (net (code "25") (name "Net-(LED3-Pad1)") (class "Default")
      (node (ref "LED3") (pin "1") (pinfunction "1_1") (pintype "passive"))
      (node (ref "R16") (pin "1") (pinfunction "1_1") (pintype "passive"))
    )
    (net (code "26") (name "Net-(Q1-D)") (class "Default")
      (node (ref "J2") (pin "2") (pintype "passive"))
      (node (ref "Q1") (pin "3") (pinfunction "D_3") (pintype "passive"))
    )
    (net (code "27") (name "Net-(Q1-G)") (class "Default")
      (node (ref "Q1") (pin "1") (pinfunction "G_1") (pintype "passive"))
      (node (ref "R3") (pin "2") (pinfunction "2_2") (pintype "passive"))
      (node (ref "R7") (pin "2") (pinfunction "2_2") (pintype "passive"))
    )
    (net (code "28") (name "Net-(Q2-D)") (class "Default")
      (node (ref "J3") (pin "2") (pintype "passive"))
      (node (ref "Q2") (pin "3") (pinfunction "D_3") (pintype "passive"))
    )
    (net (code "29") (name "Net-(Q2-G)") (class "Default")
      (node (ref "Q2") (pin "1") (pinfunction "G_1") (pintype "passive"))
      (node (ref "R14") (pin "2") (pinfunction "2_2") (pintype "passive"))
    )
    (net (code "30") (name "Net-(U1-BOOT)") (class "Default")
      (node (ref "C3") (pin "2") (pinfunction "2_2") (pintype "passive"))
      (node (ref "U1") (pin "6") (pinfunction "BOOT_6") (pintype "power_in"))
    )
    (net (code "31") (name "Net-(U1-EN)") (class "Default")
      (node (ref "R1") (pin "1") (pinfunction "1_1") (pintype "passive"))
      (node (ref "R5") (pin "2") (pinfunction "2_2") (pintype "passive"))
      (node (ref "R6") (pin "2") (pinfunction "2_2") (pintype "passive"))
      (node (ref "TP3") (pin "1") (pinfunction "1_1") (pintype "passive"))
      (node (ref "U1") (pin "5") (pinfunction "EN_5") (pintype "input"))
    )
    (net (code "32") (name "Net-(U1-FB)") (class "Default")
      (node (ref "C6") (pin "1") (pinfunction "1_1") (pintype "passive"))
      (node (ref "C7") (pin "1") (pinfunction "1_1") (pintype "passive"))
      (node (ref "R10") (pin "2") (pinfunction "2_2") (pintype "passive"))
      (node (ref "R8") (pin "1") (pinfunction "1_1") (pintype "passive"))
      (node (ref "TP4") (pin "1") (pinfunction "1_1") (pintype "passive"))
      (node (ref "U1") (pin "4") (pinfunction "FB_4") (pintype "input"))
    )
    (net (code "33") (name "Net-(U1-SW)") (class "Default")
      (node (ref "C3") (pin "1") (pinfunction "1_1") (pintype "passive"))
      (node (ref "L1") (pin "1") (pinfunction "1_1") (pintype "passive"))
      (node (ref "U1") (pin "2") (pinfunction "SW_2") (pintype "power_in"))
    )
    (net (code "34") (name "Net-(U3-VREG_VOUT)") (class "Default")
      (node (ref "C17") (pin "2") (pinfunction "2_2") (pintype "passive"))
      (node (ref "C18") (pin "2") (pinfunction "2_2") (pintype "passive"))
      (node (ref "C19") (pin "2") (pinfunction "2_2") (pintype "passive"))
      (node (ref "U3") (pin "23") (pinfunction "DVDD_23") (pintype "power_in"))
      (node (ref "U3") (pin "45") (pinfunction "VREG_VOUT_45") (pintype "power_in"))
      (node (ref "U3") (pin "50") (pinfunction "DVDD_50") (pintype "power_in"))
    )
    (net (code "35") (name "Net-(U3-XIN)") (class "Default")
      (node (ref "C20") (pin "2") (pinfunction "2_2") (pintype "passive"))
      (node (ref "U3") (pin "20") (pinfunction "XIN_20") (pintype "input"))
      (node (ref "Y1") (pin "2") (pinfunction "2_2") (pintype "passive"))
    )
    (net (code "36") (name "Net-(U3-XOUT)") (class "Default")
      (node (ref "R15") (pin "2") (pinfunction "2_2") (pintype "passive"))
      (node (ref "U3") (pin "21") (pinfunction "XOUT_21") (pintype "output"))
    )
    (net (code "37") (name "unconnected-(J4-SWO-Pad6)") (class "Default")
      (node (ref "J4") (pin "6") (pinfunction "SWO_6") (pintype "bidirectional+no_connect"))
    )
    (net (code "38") (name "unconnected-(J4-VCC-Pad1)") (class "Default")
      (node (ref "J4") (pin "1") (pinfunction "VCC_1") (pintype "power_in+no_connect"))
    )
    (net (code "39") (name "unconnected-(J4-~{RESET}-Pad3)") (class "Default")
      (node (ref "J4") (pin "3") (pinfunction "~{RESET}_3") (pintype "bidirectional+no_connect"))
    )
    (net (code "40") (name "unconnected-(U3-GPIO2-Pad4)") (class "Default")
      (node (ref "U3") (pin "4") (pinfunction "GPIO2_4") (pintype "bidirectional+no_connect"))
    )
    (net (code "41") (name "unconnected-(U3-GPIO6-Pad8)") (class "Default")
      (node (ref "U3") (pin "8") (pinfunction "GPIO6_8") (pintype "bidirectional+no_connect"))
    )
    (net (code "42") (name "unconnected-(U3-GPIO7-Pad9)") (class "Default")
      (node (ref "U3") (pin "9") (pinfunction "GPIO7_9") (pintype "bidirectional+no_connect"))
    )
    (net (code "43") (name "unconnected-(U3-GPIO8-Pad11)") (class "Default")
      (node (ref "U3") (pin "11") (pinfunction "GPIO8_11") (pintype "bidirectional+no_connect"))
    )
    (net (code "44") (name "unconnected-(U3-GPIO9-Pad12)") (class "Default")
      (node (ref "U3") (pin "12") (pinfunction "GPIO9_12") (pintype "bidirectional+no_connect"))
    )
    (net (code "45") (name "unconnected-(U3-GPIO13-Pad16)") (class "Default")
      (node (ref "U3") (pin "16") (pinfunction "GPIO13_16") (pintype "bidirectional+no_connect"))
    )
    (net (code "46") (name "unconnected-(U3-GPIO14-Pad17)") (class "Default")
      (node (ref "U3") (pin "17") (pinfunction "GPIO14_17") (pintype "bidirectional+no_connect"))
    )
    (net (code "47") (name "unconnected-(U3-GPIO15-Pad18)") (class "Default")
      (node (ref "U3") (pin "18") (pinfunction "GPIO15_18") (pintype "bidirectional+no_connect"))
    )
    (net (code "48") (name "unconnected-(U3-GPIO16-Pad27)") (class "Default")
      (node (ref "U3") (pin "27") (pinfunction "GPIO16_27") (pintype "bidirectional+no_connect"))
    )
    (net (code "49") (name "unconnected-(U3-GPIO17-Pad28)") (class "Default")
      (node (ref "U3") (pin "28") (pinfunction "GPIO17_28") (pintype "bidirectional+no_connect"))
    )
    (net (code "50") (name "unconnected-(U3-GPIO18-Pad29)") (class "Default")
      (node (ref "U3") (pin "29") (pinfunction "GPIO18_29") (pintype "bidirectional+no_connect"))
    )
    (net (code "51") (name "unconnected-(U3-GPIO19-Pad30)") (class "Default")
      (node (ref "U3") (pin "30") (pinfunction "GPIO19_30") (pintype "bidirectional+no_connect"))
    )
    (net (code "52") (name "unconnected-(U3-GPIO20-Pad31)") (class "Default")
      (node (ref "U3") (pin "31") (pinfunction "GPIO20_31") (pintype "bidirectional+no_connect"))
    )
    (net (code "53") (name "unconnected-(U3-GPIO21-Pad32)") (class "Default")
      (node (ref "U3") (pin "32") (pinfunction "GPIO21_32") (pintype "bidirectional+no_connect"))
    )
    (net (code "54") (name "unconnected-(U3-GPIO22-Pad34)") (class "Default")
      (node (ref "U3") (pin "34") (pinfunction "GPIO22_34") (pintype "bidirectional+no_connect"))
    )
    (net (code "55") (name "unconnected-(U3-GPIO23-Pad35)") (class "Default")
      (node (ref "U3") (pin "35") (pinfunction "GPIO23_35") (pintype "bidirectional+no_connect"))
    )
    (net (code "56") (name "unconnected-(U3-GPIO24-Pad36)") (class "Default")
      (node (ref "U3") (pin "36") (pinfunction "GPIO24_36") (pintype "bidirectional+no_connect"))
    )
    (net (code "57") (name "unconnected-(U3-GPIO25-Pad37)") (class "Default")
      (node (ref "U3") (pin "37") (pinfunction "GPIO25_37") (pintype "bidirectional+no_connect"))
    )
    (net (code "58") (name "unconnected-(U3-GPIO27{slash}ADC1-Pad39)") (class "Default")
      (node (ref "U3") (pin "39") (pinfunction "GPIO27/ADC1_39") (pintype "bidirectional+no_connect"))
    )
    (net (code "59") (name "unconnected-(U3-GPIO28{slash}ADC2-Pad40)") (class "Default")
      (node (ref "U3") (pin "40") (pinfunction "GPIO28/ADC2_40") (pintype "bidirectional+no_connect"))
    )
    (net (code "60") (name "unconnected-(U3-GPIO29{slash}ADC3-Pad41)") (class "Default")
      (node (ref "U3") (pin "41") (pinfunction "GPIO29/ADC3_41") (pintype "bidirectional+no_connect"))
    )
    (net (code "61") (name "unconnected-(U3-USB_DM-Pad46)") (class "Default")
      (node (ref "U3") (pin "46") (pinfunction "USB_DM_46") (pintype "bidirectional+no_connect"))
    )
    (net (code "62") (name "unconnected-(U3-USB_DP-Pad47)") (class "Default")
      (node (ref "U3") (pin "47") (pinfunction "USB_DP_47") (pintype "bidirectional+no_connect"))
    )
  )
)
